# USB_PWR_CLK.net
KiCad netlist of a schematic drawn in Altium Designer
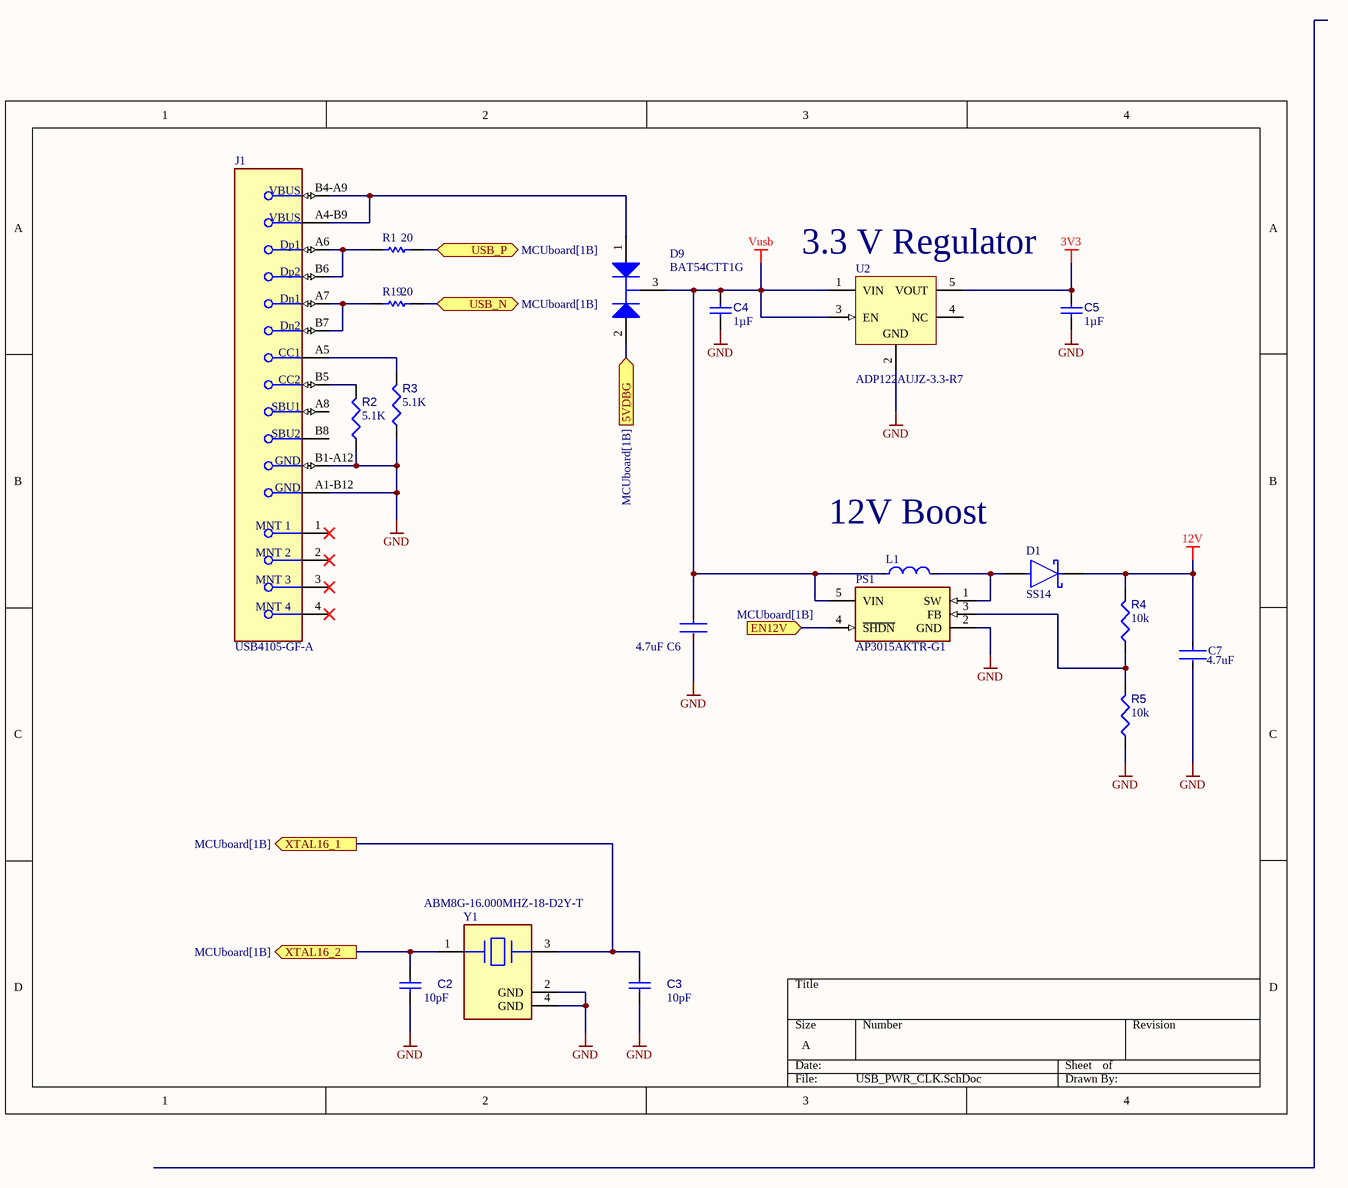
[diagram p0: USB_PWR_CLK.SchDoc]

(export (version "E")
  (design (tool "Eeschema 10.0.6"))
  (components
    (comp (ref "C2")
      (value "10pF")
      (footprint "CAPC1608X87X35NL15T15")
      (description "Chip Capacitor, 10 pF, +/- 0.25 pF, 50 V, 0603 (1608 Metric)")
      (fields
        (field (name "TOLERANCE") "0.25%")
        (field (name "Comment") "Capacitor 10 pF +/- 0.25 pF 50 V 0603")
      )
      (libsource (lib "Nebraska Instruments") (part "CAP-NP-2"))
    )
    (comp (ref "C3")
      (value "10pF")
      (footprint "CAPC1608X87X35NL15T15")
      (description "Chip Capacitor, 10 pF, +/- 0.25 pF, 50 V, 0603 (1608 Metric)")
      (fields
        (field (name "TOLERANCE") "0.25%")
        (field (name "Comment") "Capacitor 10 pF +/- 0.25 pF 50 V 0603")
      )
      (libsource (lib "Nebraska Instruments") (part "CAP-NP-2"))
    )
    (comp (ref "C4")
      (value "1µF")
      (footprint "CAPC1608X90X35ML15T15")
      (description "Chip Capacitor, 1 uF, +/- 10%, 16 V, 0603 (1608 Metric)")
      (fields (field (name "TOLERANCE") "10%") (field (name "Comment") "Capacitor 1uF +/- 10% 16V 0603"))
      (libsource (lib "Nebraska Instruments") (part "CAP-NP-2"))
    )
    (comp (ref "C5")
      (value "1µF")
      (footprint "CAPC1608X90X35ML15T15")
      (description "Chip Capacitor, 1 uF, +/- 10%, 16 V, 0603 (1608 Metric)")
      (fields (field (name "TOLERANCE") "10%") (field (name "Comment") "Capacitor 1uF +/- 10% 16V 0603"))
      (libsource (lib "Nebraska Instruments") (part "CAP-NP-2"))
    )
    (comp (ref "C6")
      (value "GRM188R61E475KE11D")
      (footprint "FP-GRM188-0_15-IPC_C")
      (description "Chip Multilayer Ceramic Capacitors for General Purpose, 0603, 4.7uF, X5R, 15%, 10%, 25V")
      (fields
        (field (name "CAPACITANCE") "4.7uF")
        (field (name "VOLTAGE") "25V")
        (field (name "TOLERANCE") "10%")
      )
      (libsource (lib "Altium Content Vault") (part "02cd4be3c70576c341d710602a673aa"))
    )
    (comp (ref "C7")
      (value "GRM188R61E475KE11D")
      (footprint "FP-GRM188-0_15-IPC_C")
      (description "Chip Multilayer Ceramic Capacitors for General Purpose, 0603, 4.7uF, X5R, 15%, 10%, 25V")
      (fields
        (field (name "CAPACITANCE") "4.7uF")
        (field (name "VOLTAGE") "25V")
        (field (name "TOLERANCE") "10%")
      )
      (libsource (lib "Altium Content Vault") (part "02cd4be3c70576c341d710602a673aa"))
    )
    (comp (ref "D1")
      (value "SS14")
      (footprint "FP-403AE-MFG")
      (description "DIODE SCHOTTKY 40V 1A SMA")
      (fields
        (field (name "MANUFACTURER") "ON Semiconductor")
        (field (name "OCTOPART") "https://octopart.com/ss14-on+semiconductor-29205033")
      )
      (libsource (lib "Altium Content Vault") (part "360ad2f4ac25a952324d13796385471"))
    )
    (comp (ref "D9")
      (value "BAT54CTT1G")
      (footprint "ONSC-SC-75-3-463-01_V")
      (description "Dual Series Cathode Schottky Barrier Diodes, 3-Pin SC-75, Pb-Free, Tape and Reel")
      (fields (field (name "MANUFACTURER") "On Semiconductor"))
      (libsource (lib "Altium Content Vault") (part "ONSC-D-A1A2K3-3"))
    )
    (comp (ref "J1")
      (value "USB4105-GF-A")
      (footprint "FP-USB4105-GF-A-MFG")
      (description "Conn USB 2.0 Type C RCP 24 POS 0.3mm/0.5mm Solder RA SMD 24 Terminal 1 Port T/R")
      (libsource (lib "Nebraska Instruments") (part "e7c17a616881a82b79941196b4bec10"))
    )
    (comp (ref "L1")
      (value "MLZ2012N100LT000")
      (footprint "FP-MLZ2012-1_25-MFG")
      (description "Shielded Multilayer Inductor 10uH ±20% 500mA 390mΩ SMD 0805")
      (fields (field (name "TOLERANCE") "20%"))
      (libsource (lib "Altium Content Vault") (part "725321dda6339637d4d059423bc1c3c"))
    )
    (comp (ref "PS1")
      (value "AP3015AKTR-G1")
      (footprint "SamacSys:SOT95P280X145-5N")
      (description "Power Supply")
      (fields (field (name "MOUSER PART NUMBER") "621-AP3015AKTR-G1"))
      (libsource (lib "*") (part "AP3015AKTR-G1"))
    )
    (comp (ref "R1")
      (value "ERJ3EKF1002V")
      (footprint "RESC1609X55X30LL15T15")
      (description "Chip Resistor, 10 KOhm, +/- 1%, 0.1 W, -55 to 155 degC, 0603 (1608 Metric), RoHS, Tape and Reel")
      (fields
        (field (name "RESISTANCE") "20")
        (field (name "TOLERANCE") "1%")
        (field (name "MANUFACTURER") "Panasonic")
      )
      (libsource (lib "Altium Content Vault") (part "RES-2"))
    )
    (comp (ref "R2")
      (value "5.1K")
      (footprint "RESC1608X55X25ML10T15")
      (description "Chip Resistor, 10 KOhm, +/- 1%, 01 W, -55 to 155 degC, 0603 (1608 Metric)")
      (fields (field (name "POWER") "100mW") (field (name "TOLERANCE") "1%"))
      (libsource (lib "Nebraska Instruments") (part "RES-2"))
    )
    (comp (ref "R3")
      (value "5.1K")
      (footprint "RESC1608X55X25ML10T15")
      (description "Chip Resistor, 10 KOhm, +/- 1%, 01 W, -55 to 155 degC, 0603 (1608 Metric)")
      (fields (field (name "POWER") "100mW") (field (name "TOLERANCE") "1%"))
      (libsource (lib "Nebraska Instruments") (part "RES-2"))
    )
    (comp (ref "R4")
      (value "10k")
      (footprint "RESC1608X55X25ML10T15")
      (description "Chip Resistor, 10 KOhm, +/- 1%, 01 W, -55 to 155 degC, 0603 (1608 Metric)")
      (fields (field (name "POWER") "100mW") (field (name "TOLERANCE") "1%"))
      (libsource (lib "Nebraska Instruments") (part "RES-2"))
    )
    (comp (ref "R5")
      (value "10k")
      (footprint "RESC1608X55X25ML10T15")
      (description "Chip Resistor, 10 KOhm, +/- 1%, 01 W, -55 to 155 degC, 0603 (1608 Metric)")
      (fields (field (name "POWER") "100mW") (field (name "TOLERANCE") "1%"))
      (libsource (lib "Nebraska Instruments") (part "RES-2"))
    )
    (comp (ref "R19")
      (value "ERJ3EKF1002V")
      (footprint "RESC1609X55X30LL15T15")
      (description "Chip Resistor, 10 KOhm, +/- 1%, 0.1 W, -55 to 155 degC, 0603 (1608 Metric), RoHS, Tape and Reel")
      (fields
        (field (name "RESISTANCE") "20")
        (field (name "TOLERANCE") "1%")
        (field (name "MANUFACTURER") "Panasonic")
      )
      (libsource (lib "Altium Content Vault") (part "RES-2"))
    )
    (comp (ref "U2")
      (value "ADP122AUJZ-3.3-R7")
      (footprint "ADI-UJ-5_M")
      (fields (field (name "MANUFACTURER") "Analog Devices"))
      (libsource (lib "Altium Content Vault") (part "ADI-ADP1XX-UJ-5"))
    )
    (comp (ref "Y1")
      (value "ABM8G-16.000MHZ-18-D2Y-T")
      (footprint "FP-ABM8G-MFG")
      (description "Crystal 16MHz ±20ppm (Tol) ±30ppm (Stability) 18pF FUND 80Ω 4-Pin SMD T/R")
      (fields (field (name "TOLERANCE") "20ppm"))
      (libsource (lib "Altium Content Vault") (part "48e526d86b7f2615d98721063c72f49"))
    )
  )
  (nets
    (net (code "1") (name "/5VDBG") (class "Default")
      (node (ref "D9") (pin "2") (pinfunction "A2_2") (pintype "passive"))
    )
    (net (code "2") (name "/EN12V") (class "Default")
      (node (ref "PS1") (pin "4") (pinfunction "~{SHDN}_4") (pintype "input"))
    )
    (net (code "3") (name "/USB_N") (class "Default")
      (node (ref "R19") (pin "1") (pinfunction "1_1") (pintype "passive"))
    )
    (net (code "4") (name "/USB_P") (class "Default")
      (node (ref "R1") (pin "1") (pinfunction "1_1") (pintype "passive"))
    )
    (net (code "5") (name "/XTAL16_1") (class "Default")
      (node (ref "C3") (pin "1") (pinfunction "1_1") (pintype "passive"))
      (node (ref "Y1") (pin "3") (pinfunction "3_3") (pintype "passive"))
    )
    (net (code "6") (name "/XTAL16_2") (class "Default")
      (node (ref "C2") (pin "1") (pinfunction "1_1") (pintype "passive"))
      (node (ref "Y1") (pin "1") (pinfunction "1_1") (pintype "passive"))
    )
    (net (code "7") (name "3V3") (class "Default")
      (node (ref "C5") (pin "2") (pinfunction "2_2") (pintype "passive"))
      (node (ref "U2") (pin "5") (pinfunction "VOUT_5") (pintype "power_in"))
    )
    (net (code "8") (name "12V") (class "Default")
      (node (ref "C7") (pin "1") (pinfunction "1_1") (pintype "passive"))
      (node (ref "D1") (pin "2") (pinfunction "C_2") (pintype "passive"))
      (node (ref "R4") (pin "2") (pinfunction "2_2") (pintype "passive"))
    )
    (net (code "9") (name "GND") (class "Default")
      (node (ref "C2") (pin "2") (pinfunction "2_2") (pintype "passive"))
      (node (ref "C3") (pin "2") (pinfunction "2_2") (pintype "passive"))
      (node (ref "C4") (pin "1") (pinfunction "1_1") (pintype "passive"))
      (node (ref "C5") (pin "1") (pinfunction "1_1") (pintype "passive"))
      (node (ref "C6") (pin "2") (pinfunction "2_2") (pintype "passive"))
      (node (ref "C7") (pin "2") (pinfunction "2_2") (pintype "passive"))
      (node (ref "J1") (pin "A1-B12") (pinfunction "GND_A1-B12") (pintype "power_in"))
      (node (ref "J1") (pin "B1-A12") (pinfunction "GND_B1-A12") (pintype "bidirectional"))
      (node (ref "PS1") (pin "2") (pinfunction "GND_2") (pintype "power_in"))
      (node (ref "R2") (pin "1") (pinfunction "1_1") (pintype "passive"))
      (node (ref "R3") (pin "1") (pinfunction "1_1") (pintype "passive"))
      (node (ref "R5") (pin "1") (pinfunction "1_1") (pintype "passive"))
      (node (ref "U2") (pin "2") (pinfunction "GND_2") (pintype "power_in"))
      (node (ref "Y1") (pin "2") (pinfunction "GND_2") (pintype "power_in"))
      (node (ref "Y1") (pin "4") (pinfunction "GND_4") (pintype "power_in"))
    )
    (net (code "10") (name "Net-(D1-A)") (class "Default")
      (node (ref "D1") (pin "1") (pinfunction "A_1") (pintype "passive"))
      (node (ref "L1") (pin "2") (pinfunction "2_2") (pintype "passive"))
      (node (ref "PS1") (pin "1") (pinfunction "SW_1") (pintype "input"))
    )
    (net (code "11") (name "Net-(D9-A1)") (class "Default")
      (node (ref "D9") (pin "1") (pinfunction "A1_1") (pintype "passive"))
      (node (ref "J1") (pin "A4-B9") (pinfunction "VBUS_A4-B9") (pintype "power_in"))
      (node (ref "J1") (pin "B4-A9") (pinfunction "VBUS_B4-A9") (pintype "bidirectional"))
    )
    (net (code "12") (name "Net-(J1-CC1)") (class "Default")
      (node (ref "J1") (pin "A5") (pinfunction "CC1_A5") (pintype "power_in"))
      (node (ref "R3") (pin "2") (pinfunction "2_2") (pintype "passive"))
    )
    (net (code "13") (name "Net-(J1-CC2)") (class "Default")
      (node (ref "J1") (pin "B5") (pinfunction "CC2_B5") (pintype "bidirectional"))
      (node (ref "R2") (pin "2") (pinfunction "2_2") (pintype "passive"))
    )
    (net (code "14") (name "Net-(J1-Dn1)") (class "Default")
      (node (ref "J1") (pin "A7") (pinfunction "Dn1_A7") (pintype "bidirectional"))
      (node (ref "J1") (pin "B7") (pinfunction "Dn2_B7") (pintype "bidirectional"))
      (node (ref "R19") (pin "2") (pinfunction "2_2") (pintype "passive"))
    )
    (net (code "15") (name "Net-(J1-Dp1)") (class "Default")
      (node (ref "J1") (pin "A6") (pinfunction "Dp1_A6") (pintype "bidirectional"))
      (node (ref "J1") (pin "B6") (pinfunction "Dp2_B6") (pintype "bidirectional"))
      (node (ref "R1") (pin "2") (pinfunction "2_2") (pintype "passive"))
    )
    (net (code "16") (name "Net-(PS1-FB)") (class "Default")
      (node (ref "PS1") (pin "3") (pinfunction "FB_3") (pintype "input"))
      (node (ref "R4") (pin "1") (pinfunction "1_1") (pintype "passive"))
      (node (ref "R5") (pin "2") (pinfunction "2_2") (pintype "passive"))
    )
    (net (code "17") (name "Vusb") (class "Default")
      (node (ref "C4") (pin "2") (pinfunction "2_2") (pintype "passive"))
      (node (ref "C6") (pin "1") (pinfunction "1_1") (pintype "passive"))
      (node (ref "D9") (pin "3") (pinfunction "K_3") (pintype "passive"))
      (node (ref "L1") (pin "1") (pinfunction "1_1") (pintype "passive"))
      (node (ref "PS1") (pin "5") (pinfunction "VIN_5") (pintype "power_in"))
      (node (ref "U2") (pin "1") (pinfunction "VIN_1") (pintype "power_in"))
      (node (ref "U2") (pin "3") (pinfunction "EN_3") (pintype "input"))
    )
    (net (code "18") (name "unconnected-(J1-MNT_1-Pad1)") (class "Default")
      (node (ref "J1") (pin "1") (pinfunction "MNT_1_1") (pintype "power_in+no_connect"))
    )
    (net (code "19") (name "unconnected-(J1-MNT_2-Pad2)") (class "Default")
      (node (ref "J1") (pin "2") (pinfunction "MNT_2_2") (pintype "power_in+no_connect"))
    )
    (net (code "20") (name "unconnected-(J1-MNT_3-Pad3)") (class "Default")
      (node (ref "J1") (pin "3") (pinfunction "MNT_3_3") (pintype "power_in+no_connect"))
    )
    (net (code "21") (name "unconnected-(J1-MNT_4-Pad4)") (class "Default")
      (node (ref "J1") (pin "4") (pinfunction "MNT_4_4") (pintype "power_in+no_connect"))
    )
    (net (code "22") (name "unconnected-(J1-SBU1-PadA8)") (class "Default")
      (node (ref "J1") (pin "A8") (pinfunction "SBU1_A8") (pintype "bidirectional"))
    )
    (net (code "23") (name "unconnected-(J1-SBU2-PadB8)") (class "Default")
      (node (ref "J1") (pin "B8") (pinfunction "SBU2_B8") (pintype "power_in"))
    )
    (net (code "24") (name "unconnected-(U2-NC-Pad4)") (class "Default")
      (node (ref "U2") (pin "4") (pinfunction "NC_4") (pintype "passive"))
    )
  )
)
